# CutMonitor_Power.net
KiCad netlist of a schematic drawn in Altium Designer
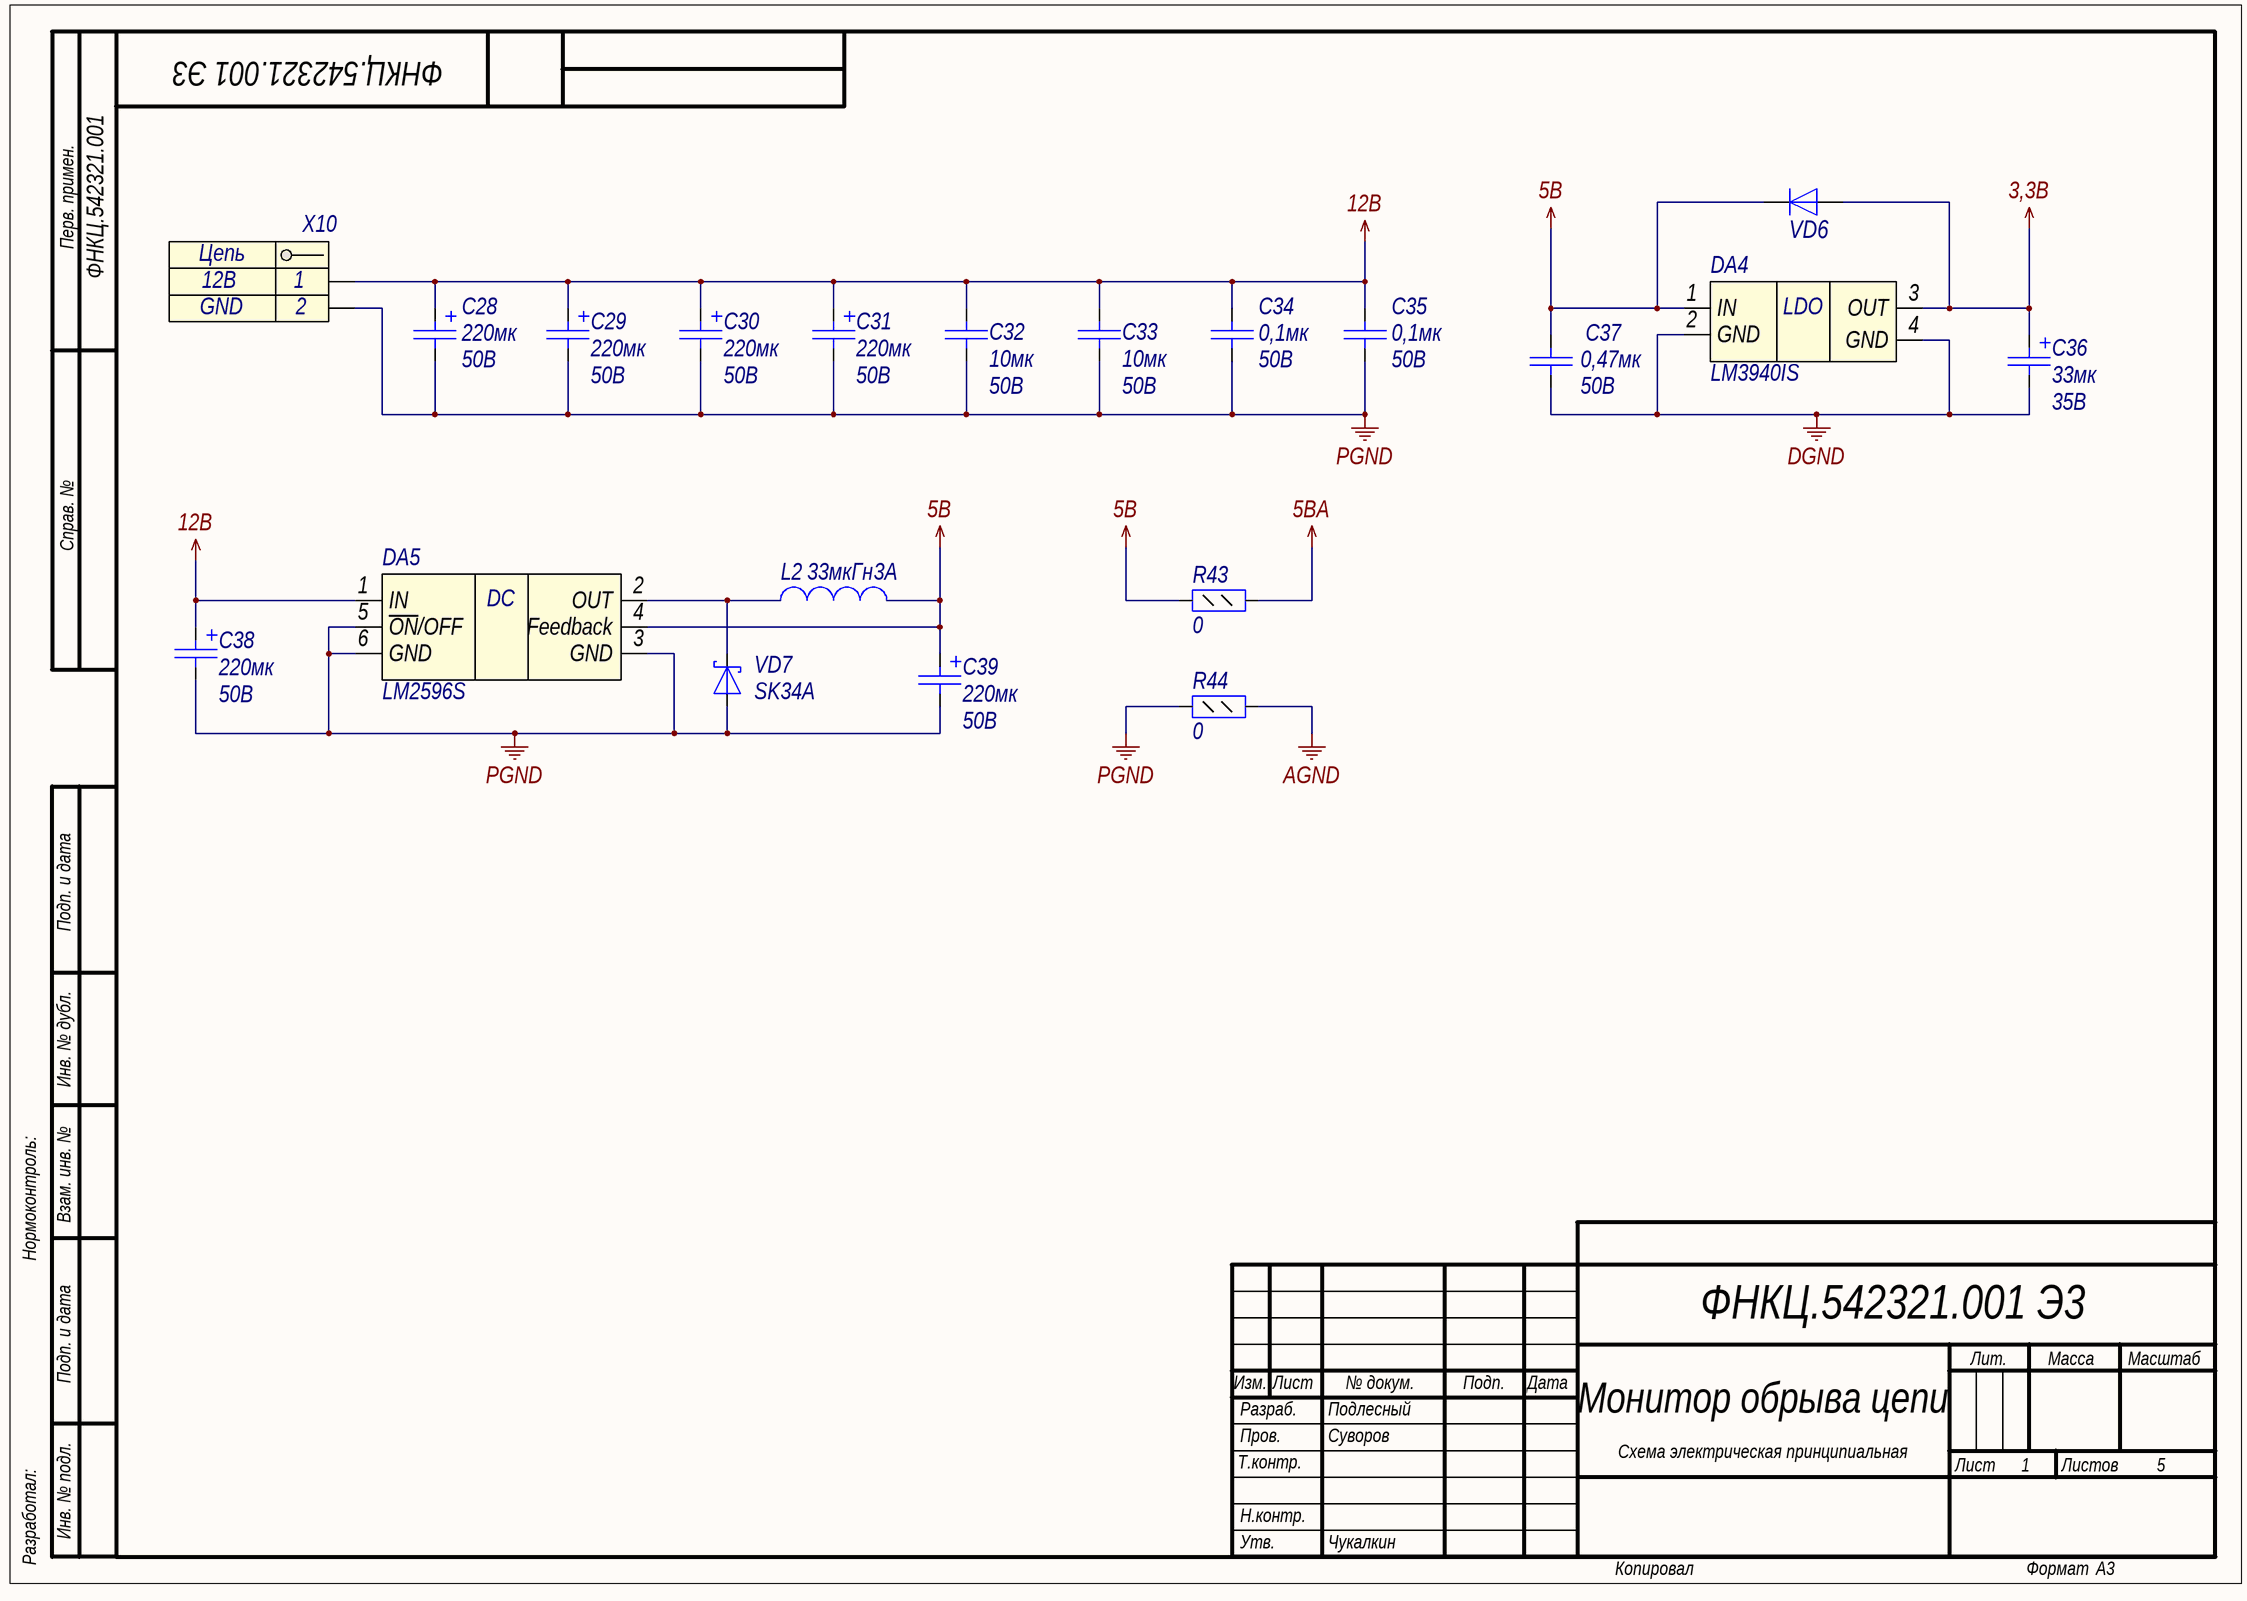
[diagram p0: CutMonitor_Power.SchDoc]

(export (version "E")
  (design (tool "Eeschema 10.0.6"))
  (components
    (comp (ref "C28")
      (value "220мк")
      (footprint "K50-35(10X12.5)")
      (description "Конденсатор полярный")
      (fields
        (field (name "VOLTAGE") "50В")
        (field (name "PART NUMBER") "TKR221M1HG13")
        (field (name "Comment") "Capacitor_pol")
      )
      (libsource (lib "MOP44") (part "Capacitor_pol"))
    )
    (comp (ref "C29")
      (value "220мк")
      (footprint "K50-35(10X12.5)")
      (description "Конденсатор полярный")
      (fields
        (field (name "VOLTAGE") "50В")
        (field (name "PART NUMBER") "TKR221M1HG13")
        (field (name "Comment") "Capacitor_pol")
      )
      (libsource (lib "MOP44") (part "Capacitor_pol"))
    )
    (comp (ref "C30")
      (value "220мк")
      (footprint "K50-35(10X12.5)_MIRROR")
      (description "Конденсатор полярный")
      (fields
        (field (name "VOLTAGE") "50В")
        (field (name "PART NUMBER") "TKR221M1HG13")
        (field (name "Comment") "Capacitor_pol")
      )
      (libsource (lib "MOP44") (part "Capacitor_pol"))
    )
    (comp (ref "C31")
      (value "220мк")
      (footprint "K50-35(10X12.5)_MIRROR")
      (description "Конденсатор полярный")
      (fields
        (field (name "VOLTAGE") "50В")
        (field (name "PART NUMBER") "TKR221M1HG13")
        (field (name "Comment") "Capacitor_pol")
      )
      (libsource (lib "MOP44") (part "Capacitor_pol"))
    )
    (comp (ref "C32")
      (value "10мк")
      (footprint "C1210")
      (description "Конденсатор")
      (fields
        (field (name "VOLTAGE") "50В")
        (field (name "PART NUMBER") "GRM32ER71H106K")
        (field (name "Comment") "Capacitor")
      )
      (libsource (lib "MOP44") (part "Capacitor"))
    )
    (comp (ref "C33")
      (value "10мк")
      (footprint "C1210")
      (description "Конденсатор")
      (fields
        (field (name "VOLTAGE") "50В")
        (field (name "PART NUMBER") "GRM32ER71H106K")
        (field (name "Comment") "Capacitor")
      )
      (libsource (lib "MOP44") (part "Capacitor"))
    )
    (comp (ref "C34")
      (value "0,1мк")
      (footprint "C1206")
      (description "Конденсатор")
      (fields
        (field (name "VOLTAGE") "50В")
        (field (name "PART NUMBER") "GRM319R71H104K**")
        (field (name "Comment") "Capacitor")
      )
      (libsource (lib "MOP44") (part "Capacitor"))
    )
    (comp (ref "C35")
      (value "0,1мк")
      (footprint "C1206")
      (description "Конденсатор")
      (fields
        (field (name "VOLTAGE") "50В")
        (field (name "PART NUMBER") "GRM319R71H104K**")
        (field (name "Comment") "Capacitor")
      )
      (libsource (lib "MOP44") (part "Capacitor"))
    )
    (comp (ref "C36")
      (value "33мк")
      (footprint "TANTAL CASE D")
      (description "Конденсатор полярный")
      (fields
        (field (name "VOLTAGE") "35В")
        (field (name "PART NUMBER") "TAJD336K035RNJ")
        (field (name "Comment") "Capacitor_pol")
      )
      (libsource (lib "MOP44") (part "Capacitor_pol"))
    )
    (comp (ref "C37")
      (value "0,47мк")
      (footprint "C1206")
      (description "Конденсатор")
      (fields
        (field (name "VOLTAGE") "50В")
        (field (name "PART NUMBER") "GRM31MR71H474K")
        (field (name "Comment") "Capacitor")
      )
      (libsource (lib "MOP44") (part "Capacitor"))
    )
    (comp (ref "C38")
      (value "220мк")
      (footprint "K50-35(10X12.5)_MIRROR")
      (description "Конденсатор полярный")
      (fields
        (field (name "VOLTAGE") "50В")
        (field (name "PART NUMBER") "TKR221M1HG13")
        (field (name "Comment") "Capacitor_pol")
      )
      (libsource (lib "MOP44") (part "Capacitor_pol"))
    )
    (comp (ref "C39")
      (value "220мк")
      (footprint "K50-35(10X12.5)_MIRROR")
      (description "Конденсатор полярный")
      (fields
        (field (name "VOLTAGE") "50В")
        (field (name "PART NUMBER") "TKR221M1HG13")
        (field (name "Comment") "Capacitor_pol")
      )
      (libsource (lib "MOP44") (part "Capacitor_pol"))
    )
    (comp (ref "DA4")
      (value "LM3940IS")
      (footprint "TO-263-3")
      (description "Low-Dropout Regulator for 5-V to 3.3-V Conversion")
      (fields
        (field (name "PART NUMBER") "LM3940IS-3.3/NOPB")
        (field (name "MANUFACTURER") "Texas Instruments")
      )
      (libsource (lib "MOP44") (part "LM3940IS"))
    )
    (comp (ref "DA5")
      (value "LM2596S")
      (footprint "TO-263-5")
      (description "3-A Step-Down Voltage Regulator")
      (fields
        (field (name "PART NUMBER") "LM2596S-5.0/NOPB")
        (field (name "MANUFACTURER") "Texas Instruments")
      )
      (libsource (lib "MOP44") (part "LM2596S"))
    )
    (comp (ref "L2")
      (value "33мкГн")
      (footprint "IND_12.8x12.8")
      (description "EMI Suppression Filter")
      (fields
        (field (name "RATED CURRENT") "3A")
        (field (name "PART NUMBER") "B82477G4333M000")
        (field (name "Comment") "Inductor")
      )
      (libsource (lib "MOP44") (part "Inductor"))
    )
    (comp (ref "R43")
      (value "0")
      (footprint "R0805")
      (description "Резистор")
      (fields (field (name "PART NUMBER") "RC0805FR-070RL") (field (name "POWER") "0,125Вт"))
      (libsource (lib "MOP44") (part "Resistor_0,125Вт"))
    )
    (comp (ref "R44")
      (value "0")
      (footprint "R0805")
      (description "Резистор")
      (fields (field (name "PART NUMBER") "RC0805FR-070RL") (field (name "POWER") "0,125Вт"))
      (libsource (lib "MOP44") (part "Resistor_0,125Вт"))
    )
    (comp (ref "VD6")
      (value "Diode")
      (footprint "SOD-523")
      (description "Диод")
      (fields (field (name "PART NUMBER") "BAS516.135"))
      (libsource (lib "MOP44") (part "Diode"))
    )
    (comp (ref "VD7")
      (value "DiodeSchottky")
      (footprint "SMA")
      (description "Диод Шоттки")
      (fields (field (name "PART NUMBER") "SK34A"))
      (libsource (lib "MOP44") (part "DiodeSchottky"))
    )
    (comp (ref "X10")
      (value "Header_2_trm")
      (footprint "TERMINAL-2WAY-5MM")
      (description "Разъем - 2 конт. клеммник")
      (libsource (lib "MOP44") (part "Header_2_trm"))
    )
  )
  (nets
    (net (code "1") (name "3,3B") (class "Default")
      (node (ref "C36") (pin "1") (pinfunction "1_1") (pintype "passive"))
      (node (ref "DA4") (pin "3") (pinfunction "OUT_3") (pintype "power_in"))
      (node (ref "VD6") (pin "2") (pinfunction "A_2") (pintype "passive"))
    )
    (net (code "2") (name "5B") (class "Default")
      (node (ref "C37") (pin "2") (pinfunction "2_2") (pintype "passive"))
      (node (ref "C39") (pin "1") (pinfunction "1_1") (pintype "passive"))
      (node (ref "DA4") (pin "1") (pinfunction "IN_1") (pintype "power_in"))
      (node (ref "DA5") (pin "4") (pinfunction "Feedback_4") (pintype "power_in"))
      (node (ref "L2") (pin "2") (pinfunction "2_2") (pintype "passive"))
      (node (ref "R43") (pin "1") (pinfunction "1_1") (pintype "passive"))
      (node (ref "VD6") (pin "1") (pinfunction "K_1") (pintype "passive"))
    )
    (net (code "3") (name "5BA") (class "Default")
      (node (ref "R43") (pin "2") (pinfunction "2_2") (pintype "passive"))
    )
    (net (code "4") (name "12B") (class "Default")
      (node (ref "C28") (pin "1") (pinfunction "1_1") (pintype "passive"))
      (node (ref "C29") (pin "1") (pinfunction "1_1") (pintype "passive"))
      (node (ref "C30") (pin "1") (pinfunction "1_1") (pintype "passive"))
      (node (ref "C31") (pin "1") (pinfunction "1_1") (pintype "passive"))
      (node (ref "C32") (pin "1") (pinfunction "1_1") (pintype "passive"))
      (node (ref "C33") (pin "1") (pinfunction "1_1") (pintype "passive"))
      (node (ref "C34") (pin "1") (pinfunction "1_1") (pintype "passive"))
      (node (ref "C35") (pin "1") (pinfunction "1_1") (pintype "passive"))
      (node (ref "C38") (pin "1") (pinfunction "1_1") (pintype "passive"))
      (node (ref "DA5") (pin "1") (pinfunction "IN_1") (pintype "power_in"))
      (node (ref "X10") (pin "1") (pinfunction "1_1") (pintype "passive"))
    )
    (net (code "5") (name "AGND") (class "Default")
      (node (ref "R44") (pin "2") (pinfunction "2_2") (pintype "passive"))
    )
    (net (code "6") (name "DGND") (class "Default")
      (node (ref "C36") (pin "2") (pinfunction "2_2") (pintype "passive"))
      (node (ref "C37") (pin "1") (pinfunction "1_1") (pintype "passive"))
      (node (ref "DA4") (pin "2") (pinfunction "GND_2") (pintype "power_in"))
      (node (ref "DA4") (pin "4") (pinfunction "GND_4") (pintype "power_in"))
    )
    (net (code "7") (name "Net-(DA5-OUT)") (class "Default")
      (node (ref "DA5") (pin "2") (pinfunction "OUT_2") (pintype "power_in"))
      (node (ref "L2") (pin "1") (pinfunction "1_1") (pintype "passive"))
      (node (ref "VD7") (pin "1") (pinfunction "K_1") (pintype "passive"))
    )
    (net (code "8") (name "PGND") (class "Default")
      (node (ref "C28") (pin "2") (pinfunction "2_2") (pintype "passive"))
      (node (ref "C29") (pin "2") (pinfunction "2_2") (pintype "passive"))
      (node (ref "C30") (pin "2") (pinfunction "2_2") (pintype "passive"))
      (node (ref "C31") (pin "2") (pinfunction "2_2") (pintype "passive"))
      (node (ref "C32") (pin "2") (pinfunction "2_2") (pintype "passive"))
      (node (ref "C33") (pin "2") (pinfunction "2_2") (pintype "passive"))
      (node (ref "C34") (pin "2") (pinfunction "2_2") (pintype "passive"))
      (node (ref "C35") (pin "2") (pinfunction "2_2") (pintype "passive"))
      (node (ref "C38") (pin "2") (pinfunction "2_2") (pintype "passive"))
      (node (ref "C39") (pin "2") (pinfunction "2_2") (pintype "passive"))
      (node (ref "DA5") (pin "3") (pinfunction "GND_3") (pintype "power_in"))
      (node (ref "DA5") (pin "5") (pinfunction "~{ON}/OFF_5") (pintype "power_in"))
      (node (ref "DA5") (pin "6") (pinfunction "GND_6") (pintype "power_in"))
      (node (ref "R44") (pin "1") (pinfunction "1_1") (pintype "passive"))
      (node (ref "VD7") (pin "2") (pinfunction "A_2") (pintype "passive"))
      (node (ref "X10") (pin "2") (pinfunction "2_2") (pintype "passive"))
    )
  )
)
